# mainSheet.net
KiCad netlist of a schematic drawn in Altium Designer
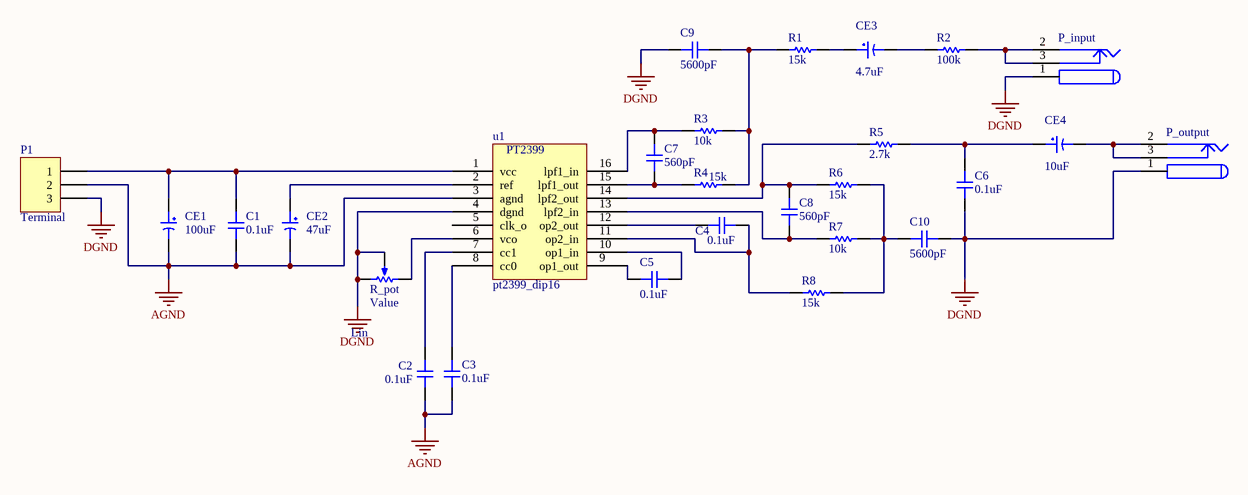
[diagram p0: mainSheet.SchDoc]

(export (version "E")
  (design (tool "Eeschema 10.0.6"))
  (components
    (comp (ref "C1")
      (value "0.1uF")
      (footprint "C100-200-100")
      (description "Capacitor")
      (fields (field (name "VOLTAGE") "100 V") (field (name "PUBLISHER") "Altium Limited"))
      (libsource (lib "GPDSE") (part "Capacitor"))
    )
    (comp (ref "C2")
      (value "0.1uF")
      (footprint "C100-200-100")
      (description "Capacitor")
      (fields (field (name "VOLTAGE") "100 V") (field (name "PUBLISHER") "Altium Limited"))
      (libsource (lib "GPDSE") (part "Capacitor"))
    )
    (comp (ref "C3")
      (value "0.1uF")
      (footprint "C100-200-100")
      (description "Capacitor")
      (fields (field (name "VOLTAGE") "100 V") (field (name "PUBLISHER") "Altium Limited"))
      (libsource (lib "GPDSE") (part "Capacitor"))
    )
    (comp (ref "C4")
      (value "0.1uF")
      (footprint "C100-200-100")
      (description "Capacitor")
      (fields (field (name "VOLTAGE") "100 V") (field (name "PUBLISHER") "Altium Limited"))
      (libsource (lib "GPDSE") (part "Capacitor"))
    )
    (comp (ref "C5")
      (value "0.1uF")
      (footprint "C100-200-100")
      (description "Capacitor")
      (fields (field (name "VOLTAGE") "100 V") (field (name "PUBLISHER") "Altium Limited"))
      (libsource (lib "GPDSE") (part "Capacitor"))
    )
    (comp (ref "C6")
      (value "0.1uF")
      (footprint "C100-200-100")
      (description "Capacitor")
      (fields (field (name "VOLTAGE") "100 V") (field (name "PUBLISHER") "Altium Limited"))
      (libsource (lib "GPDSE") (part "Capacitor"))
    )
    (comp (ref "C7")
      (value "560pF")
      (footprint "C100-200-100")
      (description "Capacitor")
      (fields (field (name "VOLTAGE") "100 V") (field (name "PUBLISHER") "Altium Limited"))
      (libsource (lib "GPDSE") (part "Capacitor"))
    )
    (comp (ref "C8")
      (value "560pF")
      (footprint "C100-200-100")
      (description "Capacitor")
      (fields (field (name "VOLTAGE") "100 V") (field (name "PUBLISHER") "Altium Limited"))
      (libsource (lib "GPDSE") (part "Capacitor"))
    )
    (comp (ref "C9")
      (value "5600pF")
      (footprint "C400-550-150")
      (description "Capacitor")
      (fields (field (name "VOLTAGE") "100 V") (field (name "PUBLISHER") "Altium Limited"))
      (libsource (lib "GPDSE") (part "Capacitor"))
    )
    (comp (ref "C10")
      (value "5600pF")
      (footprint "C400-550-150")
      (description "Capacitor")
      (fields (field (name "VOLTAGE") "100 V") (field (name "PUBLISHER") "Altium Limited"))
      (libsource (lib "GPDSE") (part "Capacitor"))
    )
    (comp (ref "CE1")
      (value "100uF")
      (footprint "CP-RAD-5.0mm-15.0mm-2.0mm")
      (description "Electrolytic Capacitor")
      (fields (field (name "VOLTAGE") "25 V"))
      (libsource (lib "") (part "Capacitor-Electrolytic_1"))
    )
    (comp (ref "CE2")
      (value "47uF")
      (footprint "PCBComponent_1")
      (description "Electrolytic Capacitor")
      (fields (field (name "VOLTAGE") "25 V"))
      (libsource (lib "") (part "Capacitor-Electrolytic_1"))
    )
    (comp (ref "CE3")
      (value "4.7uF")
      (footprint "PCBComponent_1")
      (description "Electrolytic Capacitor")
      (fields (field (name "VOLTAGE") "25 V"))
      (libsource (lib "GPDSE") (part "Capacitor-Electrolytic"))
    )
    (comp (ref "CE4")
      (value "10uF")
      (footprint "PCBComponent_1")
      (description "Electrolytic Capacitor")
      (fields (field (name "VOLTAGE") "25 V"))
      (libsource (lib "GPDSE") (part "Capacitor-Electrolytic"))
    )
    (comp (ref "P1")
      (value "Terminal")
      (footprint "KRE_3")
      (description "Terminal Block 1x3")
      (libsource (lib "GPDSE") (part "KRE_3"))
    )
    (comp (ref "P_input")
      (value "Alim")
      (footprint "jack_p2_v1")
      (description "Jack J4")
      (libsource (lib "GPDSE") (part "Jack_J4"))
    )
    (comp (ref "P_output")
      (value "Alim")
      (footprint "jack_p2_v1")
      (description "Jack J4")
      (libsource (lib "GPDSE") (part "Jack_J4"))
    )
    (comp (ref "R1")
      (value "15k")
      (footprint "R400-2.0mm")
      (description "Resistor")
      (fields
        (field (name "TOLERANCE") "5%")
        (field (name "POWER") "1/4 W")
        (field (name "PUBLISHER") "Altium Limited")
      )
      (libsource (lib "GPDSE") (part "Resistor"))
    )
    (comp (ref "R2")
      (value "100k")
      (footprint "R400-2.0mm")
      (description "Resistor")
      (fields
        (field (name "TOLERANCE") "5%")
        (field (name "POWER") "1/4 W")
        (field (name "PUBLISHER") "Altium Limited")
      )
      (libsource (lib "GPDSE") (part "Resistor"))
    )
    (comp (ref "R3")
      (value "10k")
      (footprint "R400-2.0mm")
      (description "Resistor")
      (fields
        (field (name "TOLERANCE") "5%")
        (field (name "POWER") "1/4 W")
        (field (name "PUBLISHER") "Altium Limited")
      )
      (libsource (lib "GPDSE") (part "Resistor"))
    )
    (comp (ref "R4")
      (value "15k")
      (footprint "R400-2.0mm")
      (description "Resistor")
      (fields
        (field (name "TOLERANCE") "5%")
        (field (name "POWER") "1/4 W")
        (field (name "PUBLISHER") "Altium Limited")
      )
      (libsource (lib "GPDSE") (part "Resistor"))
    )
    (comp (ref "R5")
      (value "2.7k")
      (footprint "R400-2.0mm")
      (description "Resistor")
      (fields
        (field (name "TOLERANCE") "5%")
        (field (name "POWER") "1/4 W")
        (field (name "PUBLISHER") "Altium Limited")
      )
      (libsource (lib "GPDSE") (part "Resistor"))
    )
    (comp (ref "R6")
      (value "15k")
      (footprint "R400-2.0mm")
      (description "Resistor")
      (fields
        (field (name "TOLERANCE") "5%")
        (field (name "POWER") "1/4 W")
        (field (name "PUBLISHER") "Altium Limited")
      )
      (libsource (lib "GPDSE") (part "Resistor"))
    )
    (comp (ref "R7")
      (value "10k")
      (footprint "R400-2.0mm")
      (description "Resistor")
      (fields
        (field (name "TOLERANCE") "5%")
        (field (name "POWER") "1/4 W")
        (field (name "PUBLISHER") "Altium Limited")
      )
      (libsource (lib "GPDSE") (part "Resistor"))
    )
    (comp (ref "R8")
      (value "15k")
      (footprint "R400-2.0mm")
      (description "Resistor")
      (fields
        (field (name "TOLERANCE") "5%")
        (field (name "POWER") "1/4 W")
        (field (name "PUBLISHER") "Altium Limited")
      )
      (libsource (lib "GPDSE") (part "Resistor"))
    )
    (comp (ref "R_pot")
      (value "Value")
      (footprint "POT")
      (description "Potentiometer")
      (fields (field (name "TYPE") "Lin"))
      (libsource (lib "GPDSE") (part "Potentiometer"))
    )
    (comp (ref "u1")
      (value "pt2399_dip16")
      (footprint "dip16")
      (libsource (lib "PT2399") (part "pt2399_dip16"))
    )
  )
  (nets
    (net (code "1") (name "AGND") (class "Default")
      (node (ref "C1") (pin "1") (pinfunction "1_1") (pintype "passive"))
      (node (ref "C2") (pin "1") (pinfunction "1_1") (pintype "passive"))
      (node (ref "C3") (pin "1") (pinfunction "1_1") (pintype "passive"))
      (node (ref "CE1") (pin "2") (pinfunction "2_2") (pintype "passive"))
      (node (ref "CE2") (pin "2") (pinfunction "2_2") (pintype "passive"))
      (node (ref "P1") (pin "2") (pinfunction "2_2") (pintype "passive"))
      (node (ref "u1") (pin "3") (pinfunction "agnd_3") (pintype "passive"))
    )
    (net (code "2") (name "DGND") (class "Default")
      (node (ref "C10") (pin "2") (pinfunction "2_2") (pintype "passive"))
      (node (ref "C6") (pin "2") (pinfunction "2_2") (pintype "passive"))
      (node (ref "C9") (pin "2") (pinfunction "2_2") (pintype "passive"))
      (node (ref "P1") (pin "3") (pinfunction "3_3") (pintype "passive"))
      (node (ref "P_input") (pin "1") (pinfunction "1_1") (pintype "passive"))
      (node (ref "P_output") (pin "1") (pinfunction "1_1") (pintype "passive"))
      (node (ref "R_pot") (pin "2") (pinfunction "TAP_2") (pintype "passive"))
      (node (ref "R_pot") (pin "3") (pinfunction "BOT_3") (pintype "passive"))
      (node (ref "u1") (pin "4") (pinfunction "dgnd_4") (pintype "passive"))
    )
    (net (code "3") (name "Net-(C6-Pad1)") (class "Default")
      (node (ref "C6") (pin "1") (pinfunction "1_1") (pintype "passive"))
      (node (ref "CE4") (pin "1") (pinfunction "1_1") (pintype "passive"))
      (node (ref "R5") (pin "2") (pinfunction "2_2") (pintype "passive"))
    )
    (net (code "4") (name "Net-(C9-Pad1)") (class "Default")
      (node (ref "C9") (pin "1") (pinfunction "1_1") (pintype "passive"))
      (node (ref "R1") (pin "1") (pinfunction "1_1") (pintype "passive"))
      (node (ref "R3") (pin "2") (pinfunction "2_2") (pintype "passive"))
      (node (ref "R4") (pin "2") (pinfunction "2_2") (pintype "passive"))
    )
    (net (code "5") (name "Net-(C10-Pad1)") (class "Default")
      (node (ref "C10") (pin "1") (pinfunction "1_1") (pintype "passive"))
      (node (ref "R6") (pin "2") (pinfunction "2_2") (pintype "passive"))
      (node (ref "R7") (pin "2") (pinfunction "2_2") (pintype "passive"))
      (node (ref "R8") (pin "2") (pinfunction "2_2") (pintype "passive"))
    )
    (net (code "6") (name "Net-(CE3-Pad1)") (class "Default")
      (node (ref "CE3") (pin "1") (pinfunction "1_1") (pintype "passive"))
      (node (ref "R1") (pin "2") (pinfunction "2_2") (pintype "passive"))
    )
    (net (code "7") (name "Net-(CE3-Pad2)") (class "Default")
      (node (ref "CE3") (pin "2") (pinfunction "2_2") (pintype "passive"))
      (node (ref "R2") (pin "2") (pinfunction "2_2") (pintype "passive"))
    )
    (net (code "8") (name "Net-(CE4-Pad2)") (class "Default")
      (node (ref "CE4") (pin "2") (pinfunction "2_2") (pintype "passive"))
      (node (ref "P_output") (pin "2") (pinfunction "2_2") (pintype "passive"))
      (node (ref "P_output") (pin "3") (pinfunction "3_3") (pintype "passive"))
    )
    (net (code "9") (name "Net-(P_input-Pad2)") (class "Default")
      (node (ref "P_input") (pin "2") (pinfunction "2_2") (pintype "passive"))
      (node (ref "P_input") (pin "3") (pinfunction "3_3") (pintype "passive"))
      (node (ref "R2") (pin "1") (pinfunction "1_1") (pintype "passive"))
    )
    (net (code "10") (name "Net-(R_pot-TOP)") (class "Default")
      (node (ref "R_pot") (pin "1") (pinfunction "TOP_1") (pintype "passive"))
      (node (ref "u1") (pin "6") (pinfunction "vco_6") (pintype "passive"))
    )
    (net (code "11") (name "Net-(u1-cc0)") (class "Default")
      (node (ref "C3") (pin "2") (pinfunction "2_2") (pintype "passive"))
      (node (ref "u1") (pin "8") (pinfunction "cc0_8") (pintype "passive"))
    )
    (net (code "12") (name "Net-(u1-cc1)") (class "Default")
      (node (ref "C2") (pin "2") (pinfunction "2_2") (pintype "passive"))
      (node (ref "u1") (pin "7") (pinfunction "cc1_7") (pintype "passive"))
    )
    (net (code "13") (name "Net-(u1-lpf1_in)") (class "Default")
      (node (ref "C7") (pin "2") (pinfunction "2_2") (pintype "passive"))
      (node (ref "R3") (pin "1") (pinfunction "1_1") (pintype "passive"))
      (node (ref "u1") (pin "16") (pinfunction "lpf1_in_16") (pintype "passive"))
    )
    (net (code "14") (name "Net-(u1-lpf1_out)") (class "Default")
      (node (ref "C7") (pin "1") (pinfunction "1_1") (pintype "passive"))
      (node (ref "R4") (pin "1") (pinfunction "1_1") (pintype "passive"))
      (node (ref "u1") (pin "15") (pinfunction "lpf1_out_15") (pintype "passive"))
    )
    (net (code "15") (name "Net-(u1-lpf2_in)") (class "Default")
      (node (ref "C8") (pin "1") (pinfunction "1_1") (pintype "passive"))
      (node (ref "R7") (pin "1") (pinfunction "1_1") (pintype "passive"))
      (node (ref "u1") (pin "13") (pinfunction "lpf2_in_13") (pintype "passive"))
    )
    (net (code "16") (name "Net-(u1-lpf2_out)") (class "Default")
      (node (ref "C8") (pin "2") (pinfunction "2_2") (pintype "passive"))
      (node (ref "R5") (pin "1") (pinfunction "1_1") (pintype "passive"))
      (node (ref "R6") (pin "1") (pinfunction "1_1") (pintype "passive"))
      (node (ref "u1") (pin "14") (pinfunction "lpf2_out_14") (pintype "passive"))
    )
    (net (code "17") (name "Net-(u1-op1_in)") (class "Default")
      (node (ref "C5") (pin "1") (pinfunction "1_1") (pintype "passive"))
      (node (ref "u1") (pin "10") (pinfunction "op1_in_10") (pintype "passive"))
    )
    (net (code "18") (name "Net-(u1-op1_out)") (class "Default")
      (node (ref "C5") (pin "2") (pinfunction "2_2") (pintype "passive"))
      (node (ref "u1") (pin "9") (pinfunction "op1_out_9") (pintype "passive"))
    )
    (net (code "19") (name "Net-(u1-op2_in)") (class "Default")
      (node (ref "C4") (pin "1") (pinfunction "1_1") (pintype "passive"))
      (node (ref "R8") (pin "1") (pinfunction "1_1") (pintype "passive"))
      (node (ref "u1") (pin "11") (pinfunction "op2_in_11") (pintype "passive"))
    )
    (net (code "20") (name "Net-(u1-op2_out)") (class "Default")
      (node (ref "C4") (pin "2") (pinfunction "2_2") (pintype "passive"))
      (node (ref "u1") (pin "12") (pinfunction "op2_out_12") (pintype "passive"))
    )
    (net (code "21") (name "Net-(u1-ref)") (class "Default")
      (node (ref "CE2") (pin "1") (pinfunction "1_1") (pintype "passive"))
      (node (ref "u1") (pin "2") (pinfunction "ref_2") (pintype "passive"))
    )
    (net (code "22") (name "Net-(u1-vcc)") (class "Default")
      (node (ref "C1") (pin "2") (pinfunction "2_2") (pintype "passive"))
      (node (ref "CE1") (pin "1") (pinfunction "1_1") (pintype "passive"))
      (node (ref "P1") (pin "1") (pinfunction "1_1") (pintype "passive"))
      (node (ref "u1") (pin "1") (pinfunction "vcc_1") (pintype "passive"))
    )
    (net (code "23") (name "unconnected-(u1-clk_o-Pad5)") (class "Default")
      (node (ref "u1") (pin "5") (pinfunction "clk_o_5") (pintype "passive"))
    )
  )
)
